# schematic.net
KiCad netlist of a schematic drawn in EasyEDA
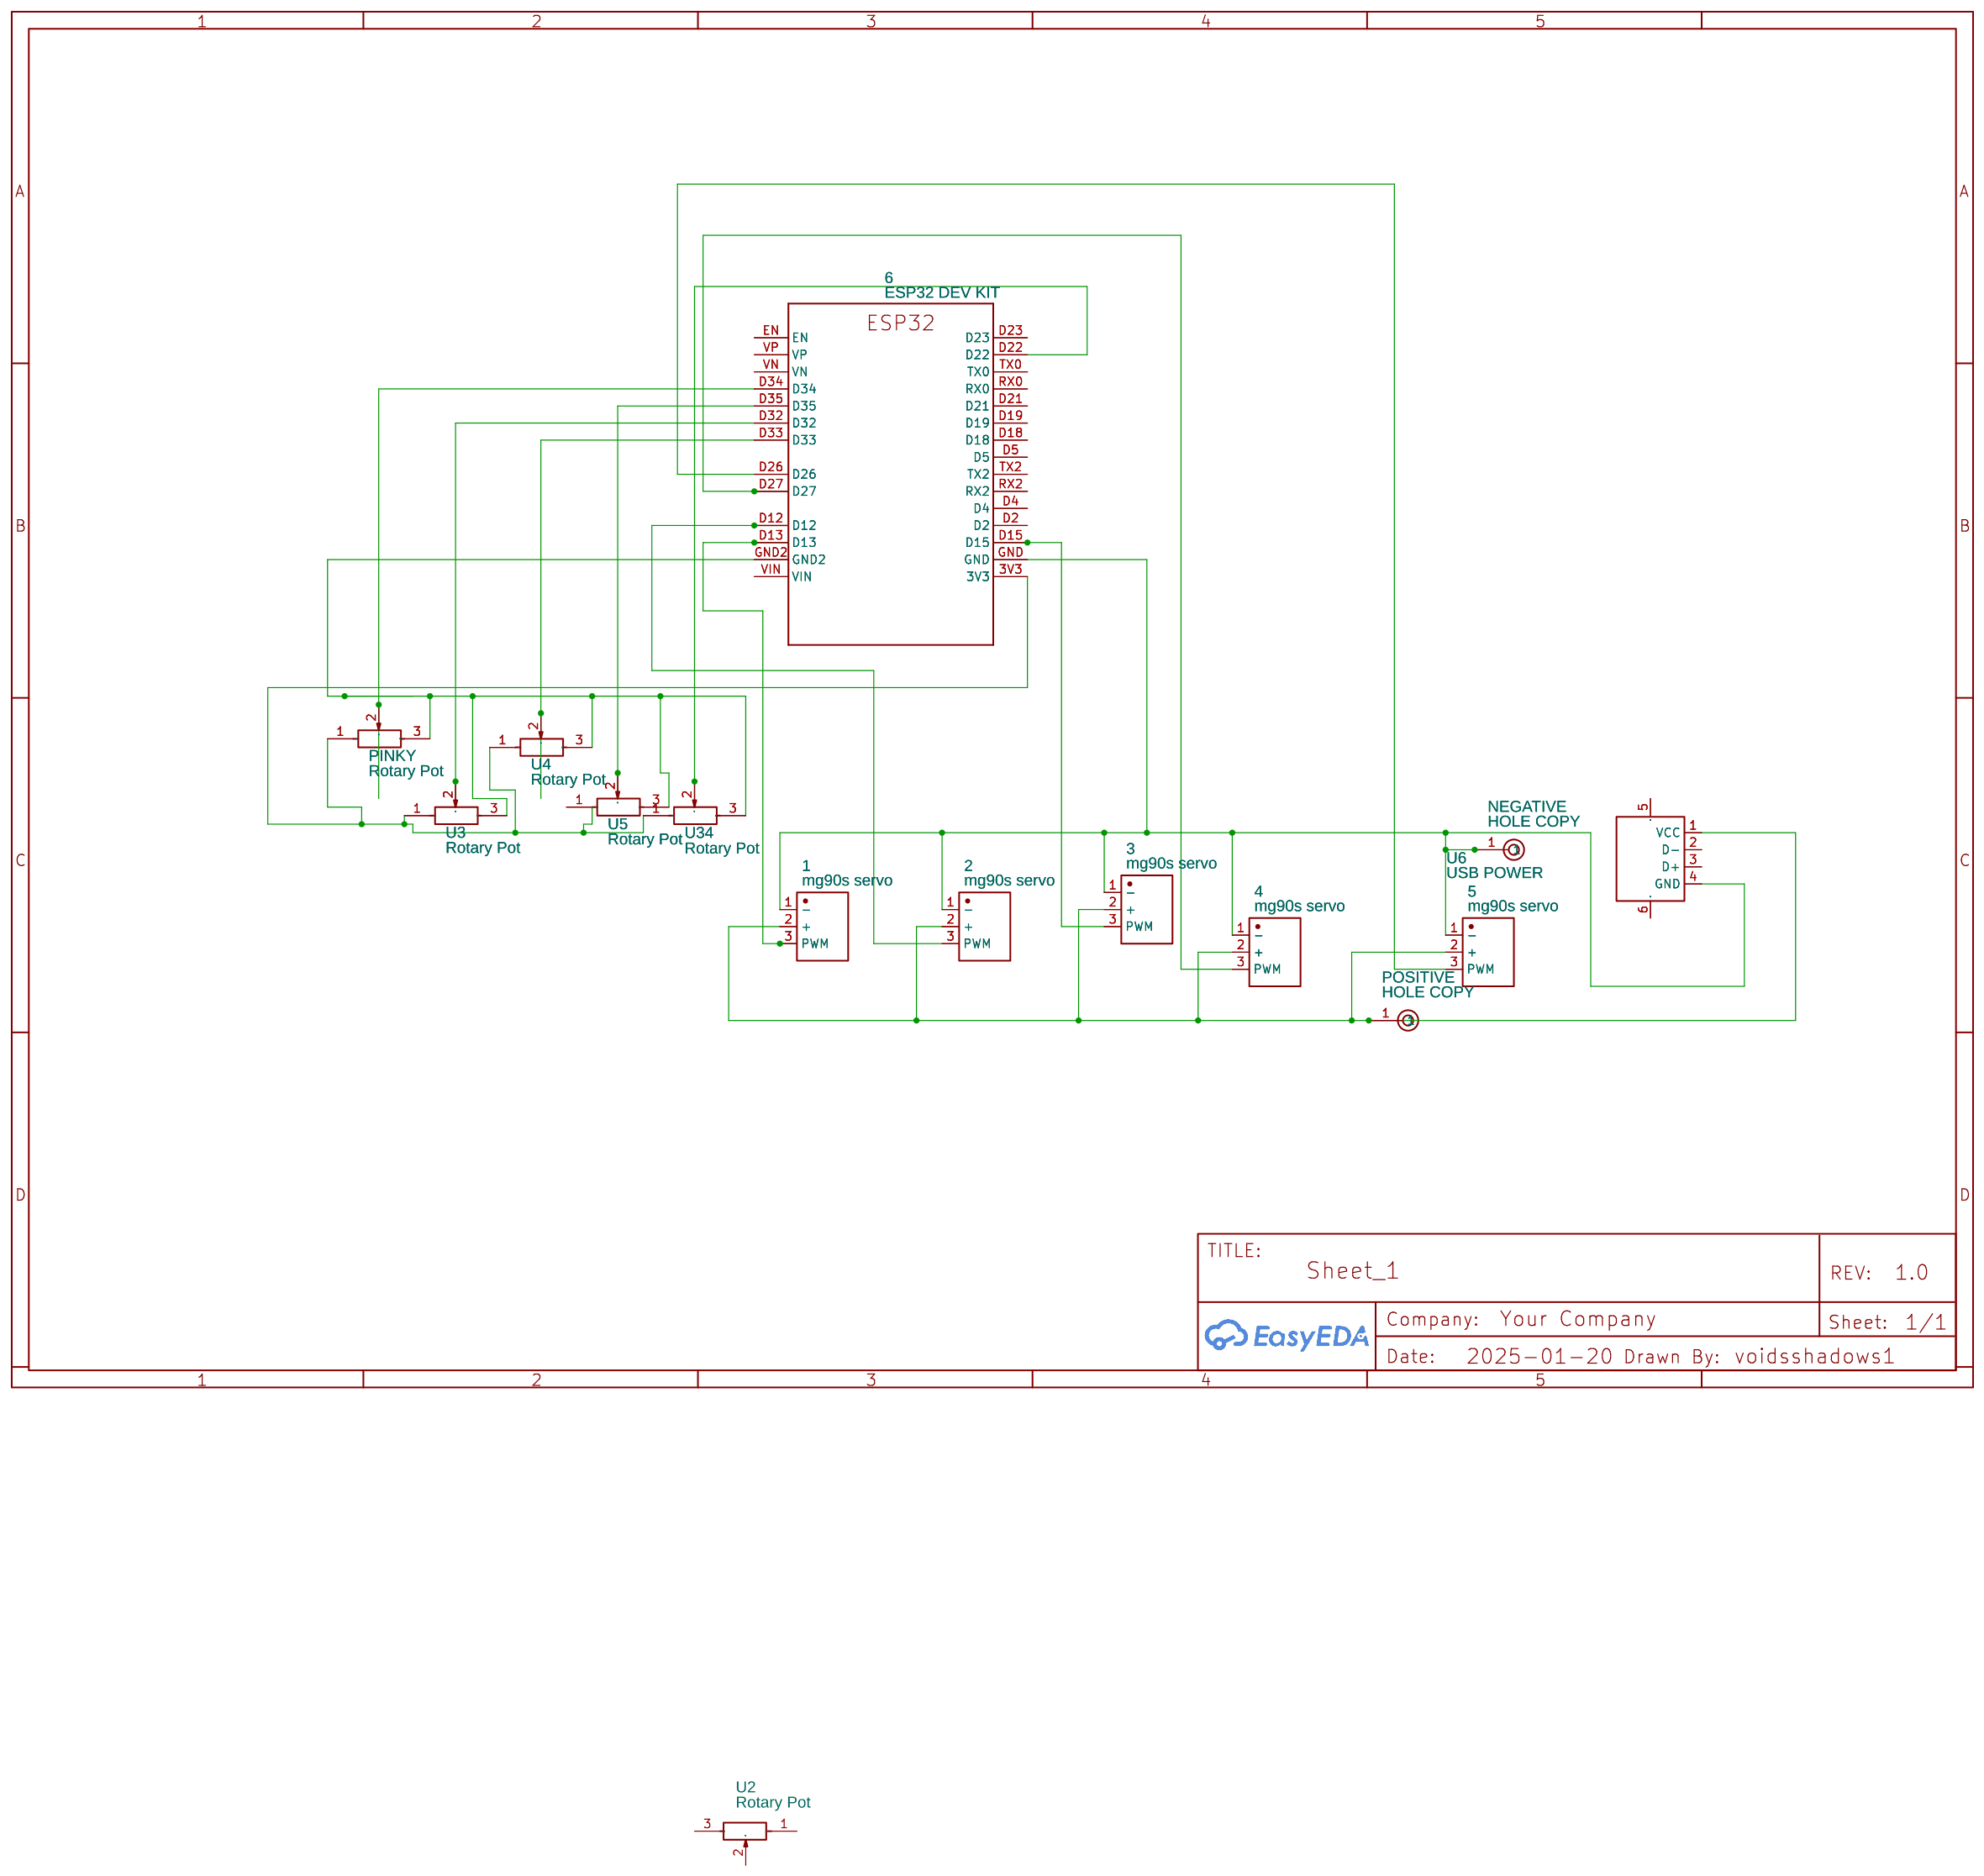
[diagram p0: schematic sheet]

(export (version "E")
  (design (tool "Eeschema 10.0.6"))
  (components
    (comp (ref "1") (value "mg90s servo") (libsource (lib "") (part "mg90s servo")))
    (comp (ref "2") (value "mg90s servo") (libsource (lib "") (part "mg90s servo")))
    (comp (ref "3") (value "mg90s servo") (libsource (lib "") (part "mg90s servo")))
    (comp (ref "4") (value "mg90s servo") (libsource (lib "") (part "mg90s servo")))
    (comp (ref "5") (value "mg90s servo") (libsource (lib "") (part "mg90s servo")))
    (comp (ref "6") (value "ESP32 DEV KIT") (libsource (lib "") (part "ESP32-DEVKIT-V1-30PIN")))
    (comp (ref "NEGATIVE") (value "HOLE COPY") (libsource (lib "") (part "HOLE COPY_1")))
    (comp (ref "PINKY") (value "Rotary Pot") (libsource (lib "") (part "Rotary Pot_2")))
    (comp (ref "POSITIVE") (value "HOLE COPY") (libsource (lib "") (part "HOLE COPY")))
    (comp (ref "U2") (value "Rotary Pot") (libsource (lib "") (part "Rotary Pot_1")))
    (comp (ref "U3") (value "Rotary Pot") (libsource (lib "") (part "Rotary Pot")))
    (comp (ref "U4") (value "Rotary Pot") (libsource (lib "") (part "Rotary Pot")))
    (comp (ref "U5") (value "Rotary Pot") (libsource (lib "") (part "Rotary Pot")))
    (comp (ref "U6")
      (value "USB POWER")
      (fields (field (name "Manufacturer Part") "USB-AF-DIP-546-HW-B") (field (name "Manufacturer") "皇捷"))
      (libsource (lib "") (part "USB-AF-DIP-546-HW-B"))
    )
    (comp (ref "U34") (value "Rotary Pot") (libsource (lib "") (part "Rotary Pot")))
  )
  (nets
    (net (code "1") (name "Net-(1-+)") (class "Default")
      (node (ref "1") (pin "2") (pinfunction "+_2") (pintype "unspecified"))
      (node (ref "2") (pin "2") (pinfunction "+_2") (pintype "unspecified"))
      (node (ref "3") (pin "2") (pinfunction "+_2") (pintype "unspecified"))
      (node (ref "4") (pin "2") (pinfunction "+_2") (pintype "unspecified"))
      (node (ref "5") (pin "2") (pinfunction "+_2") (pintype "unspecified"))
      (node (ref "POSITIVE") (pin "1") (pinfunction "1_1") (pintype "unspecified"))
      (node (ref "U6") (pin "1") (pinfunction "VCC_1") (pintype "input"))
    )
    (net (code "2") (name "Net-(1--)") (class "Default")
      (node (ref "1") (pin "1") (pinfunction "-_1") (pintype "unspecified"))
      (node (ref "2") (pin "1") (pinfunction "-_1") (pintype "unspecified"))
      (node (ref "3") (pin "1") (pinfunction "-_1") (pintype "unspecified"))
      (node (ref "4") (pin "1") (pinfunction "-_1") (pintype "unspecified"))
      (node (ref "5") (pin "1") (pinfunction "-_1") (pintype "unspecified"))
      (node (ref "6") (pin "GND") (pinfunction "GND_GND") (pintype "unspecified"))
      (node (ref "NEGATIVE") (pin "1") (pinfunction "1_1") (pintype "unspecified"))
      (node (ref "U6") (pin "4") (pinfunction "GND_4") (pintype "input"))
    )
    (net (code "3") (name "Net-(1-PWM)") (class "Default")
      (node (ref "1") (pin "3") (pinfunction "PWM_3") (pintype "unspecified"))
      (node (ref "6") (pin "D13") (pinfunction "D13_D13") (pintype "unspecified"))
    )
    (net (code "4") (name "Net-(2-PWM)") (class "Default")
      (node (ref "2") (pin "3") (pinfunction "PWM_3") (pintype "unspecified"))
      (node (ref "6") (pin "D12") (pinfunction "D12_D12") (pintype "unspecified"))
    )
    (net (code "5") (name "Net-(3-PWM)") (class "Default")
      (node (ref "3") (pin "3") (pinfunction "PWM_3") (pintype "unspecified"))
      (node (ref "6") (pin "D15") (pinfunction "D15_D15") (pintype "unspecified"))
    )
    (net (code "6") (name "Net-(4-PWM)") (class "Default")
      (node (ref "4") (pin "3") (pinfunction "PWM_3") (pintype "unspecified"))
      (node (ref "6") (pin "D27") (pinfunction "D27_D27") (pintype "unspecified"))
    )
    (net (code "7") (name "Net-(5-PWM)") (class "Default")
      (node (ref "5") (pin "3") (pinfunction "PWM_3") (pintype "unspecified"))
      (node (ref "6") (pin "D26") (pinfunction "D26_D26") (pintype "unspecified"))
    )
    (net (code "8") (name "Net-(6-Pad3V3)") (class "Default")
      (node (ref "6") (pin "3V3") (pinfunction "3V3_3V3") (pintype "unspecified"))
      (node (ref "PINKY") (pin "1") (pinfunction "1_1") (pintype "unspecified"))
      (node (ref "U3") (pin "1") (pinfunction "1_1") (pintype "unspecified"))
      (node (ref "U34") (pin "1") (pinfunction "1_1") (pintype "unspecified"))
      (node (ref "U4") (pin "1") (pinfunction "1_1") (pintype "unspecified"))
    )
    (net (code "9") (name "Net-(6-PadD22)") (class "Default")
      (node (ref "6") (pin "D22") (pinfunction "D22_D22") (pintype "unspecified"))
      (node (ref "U34") (pin "2") (pinfunction "2_2") (pintype "unspecified"))
    )
    (net (code "10") (name "Net-(6-PadD32)") (class "Default")
      (node (ref "6") (pin "D32") (pinfunction "D32_D32") (pintype "unspecified"))
      (node (ref "U3") (pin "2") (pinfunction "2_2") (pintype "unspecified"))
    )
    (net (code "11") (name "Net-(6-PadD33)") (class "Default")
      (node (ref "6") (pin "D33") (pinfunction "D33_D33") (pintype "unspecified"))
      (node (ref "U4") (pin "2") (pinfunction "2_2") (pintype "unspecified"))
    )
    (net (code "12") (name "Net-(6-PadD34)") (class "Default")
      (node (ref "6") (pin "D34") (pinfunction "D34_D34") (pintype "unspecified"))
      (node (ref "PINKY") (pin "2") (pinfunction "2_2") (pintype "unspecified"))
    )
    (net (code "13") (name "Net-(6-PadD35)") (class "Default")
      (node (ref "6") (pin "D35") (pinfunction "D35_D35") (pintype "unspecified"))
      (node (ref "U5") (pin "2") (pinfunction "2_2") (pintype "unspecified"))
    )
    (net (code "14") (name "Net-(6-PadGND2)") (class "Default")
      (node (ref "6") (pin "GND2") (pinfunction "GND2_GND2") (pintype "unspecified"))
      (node (ref "PINKY") (pin "3") (pinfunction "3_3") (pintype "unspecified"))
      (node (ref "U3") (pin "3") (pinfunction "3_3") (pintype "unspecified"))
      (node (ref "U34") (pin "3") (pinfunction "3_3") (pintype "unspecified"))
      (node (ref "U4") (pin "3") (pinfunction "3_3") (pintype "unspecified"))
      (node (ref "U5") (pin "3") (pinfunction "3_3") (pintype "unspecified"))
    )
    (net (code "15") (name "unconnected-(6-PadD2)") (class "Default")
      (node (ref "6") (pin "D2") (pinfunction "D2_D2") (pintype "unspecified"))
    )
    (net (code "16") (name "unconnected-(6-PadD4)") (class "Default")
      (node (ref "6") (pin "D4") (pinfunction "D4_D4") (pintype "unspecified"))
    )
    (net (code "17") (name "unconnected-(6-PadD5)") (class "Default")
      (node (ref "6") (pin "D5") (pinfunction "D5_D5") (pintype "unspecified"))
    )
    (net (code "18") (name "unconnected-(6-PadD18)") (class "Default")
      (node (ref "6") (pin "D18") (pinfunction "D18_D18") (pintype "unspecified"))
    )
    (net (code "19") (name "unconnected-(6-PadD19)") (class "Default")
      (node (ref "6") (pin "D19") (pinfunction "D19_D19") (pintype "unspecified"))
    )
    (net (code "20") (name "unconnected-(6-PadD21)") (class "Default")
      (node (ref "6") (pin "D21") (pinfunction "D21_D21") (pintype "unspecified"))
    )
    (net (code "21") (name "unconnected-(6-PadD23)") (class "Default")
      (node (ref "6") (pin "D23") (pinfunction "D23_D23") (pintype "unspecified"))
    )
    (net (code "22") (name "unconnected-(6-PadEN)") (class "Default")
      (node (ref "6") (pin "EN") (pinfunction "EN_EN") (pintype "unspecified"))
    )
    (net (code "23") (name "unconnected-(6-PadRX0)") (class "Default")
      (node (ref "6") (pin "RX0") (pinfunction "RX0_RX0") (pintype "unspecified"))
    )
    (net (code "24") (name "unconnected-(6-PadRX2)") (class "Default")
      (node (ref "6") (pin "RX2") (pinfunction "RX2_RX2") (pintype "unspecified"))
    )
    (net (code "25") (name "unconnected-(6-PadTX0)") (class "Default")
      (node (ref "6") (pin "TX0") (pinfunction "TX0_TX0") (pintype "unspecified"))
    )
    (net (code "26") (name "unconnected-(6-PadTX2)") (class "Default")
      (node (ref "6") (pin "TX2") (pinfunction "TX2_TX2") (pintype "unspecified"))
    )
    (net (code "27") (name "unconnected-(6-PadVIN)") (class "Default")
      (node (ref "6") (pin "VIN") (pinfunction "VIN_VIN") (pintype "unspecified"))
    )
    (net (code "28") (name "unconnected-(6-PadVN)") (class "Default")
      (node (ref "6") (pin "VN") (pinfunction "VN_VN") (pintype "unspecified"))
    )
    (net (code "29") (name "unconnected-(6-PadVP)") (class "Default")
      (node (ref "6") (pin "VP") (pinfunction "VP_VP") (pintype "unspecified"))
    )
    (net (code "30") (name "unconnected-(U2-Pad1)") (class "Default")
      (node (ref "U2") (pin "1") (pinfunction "1_1") (pintype "unspecified"))
    )
    (net (code "31") (name "unconnected-(U2-Pad2)") (class "Default")
      (node (ref "U2") (pin "2") (pinfunction "2_2") (pintype "unspecified"))
    )
    (net (code "32") (name "unconnected-(U2-Pad3)") (class "Default")
      (node (ref "U2") (pin "3") (pinfunction "3_3") (pintype "unspecified"))
    )
    (net (code "33") (name "unconnected-(U5-Pad1)") (class "Default")
      (node (ref "U5") (pin "1") (pinfunction "1_1") (pintype "unspecified"))
    )
    (net (code "34") (name "unconnected-(U6-D+-Pad3)") (class "Default")
      (node (ref "U6") (pin "3") (pinfunction "D+_3") (pintype "input"))
    )
    (net (code "35") (name "unconnected-(U6-D--Pad2)") (class "Default")
      (node (ref "U6") (pin "2") (pinfunction "D-_2") (pintype "input"))
    )
    (net (code "36") (name "unconnected-(U6-EH-Pad5)") (class "Default")
      (node (ref "U6") (pin "5") (pinfunction "EH_5") (pintype "unspecified"))
    )
    (net (code "37") (name "unconnected-(U6-EH-Pad6)") (class "Default")
      (node (ref "U6") (pin "6") (pinfunction "EH_6") (pintype "unspecified"))
    )
  )
)
